# On_Board_Computer.net
KiCad netlist of a schematic drawn in EAGLE
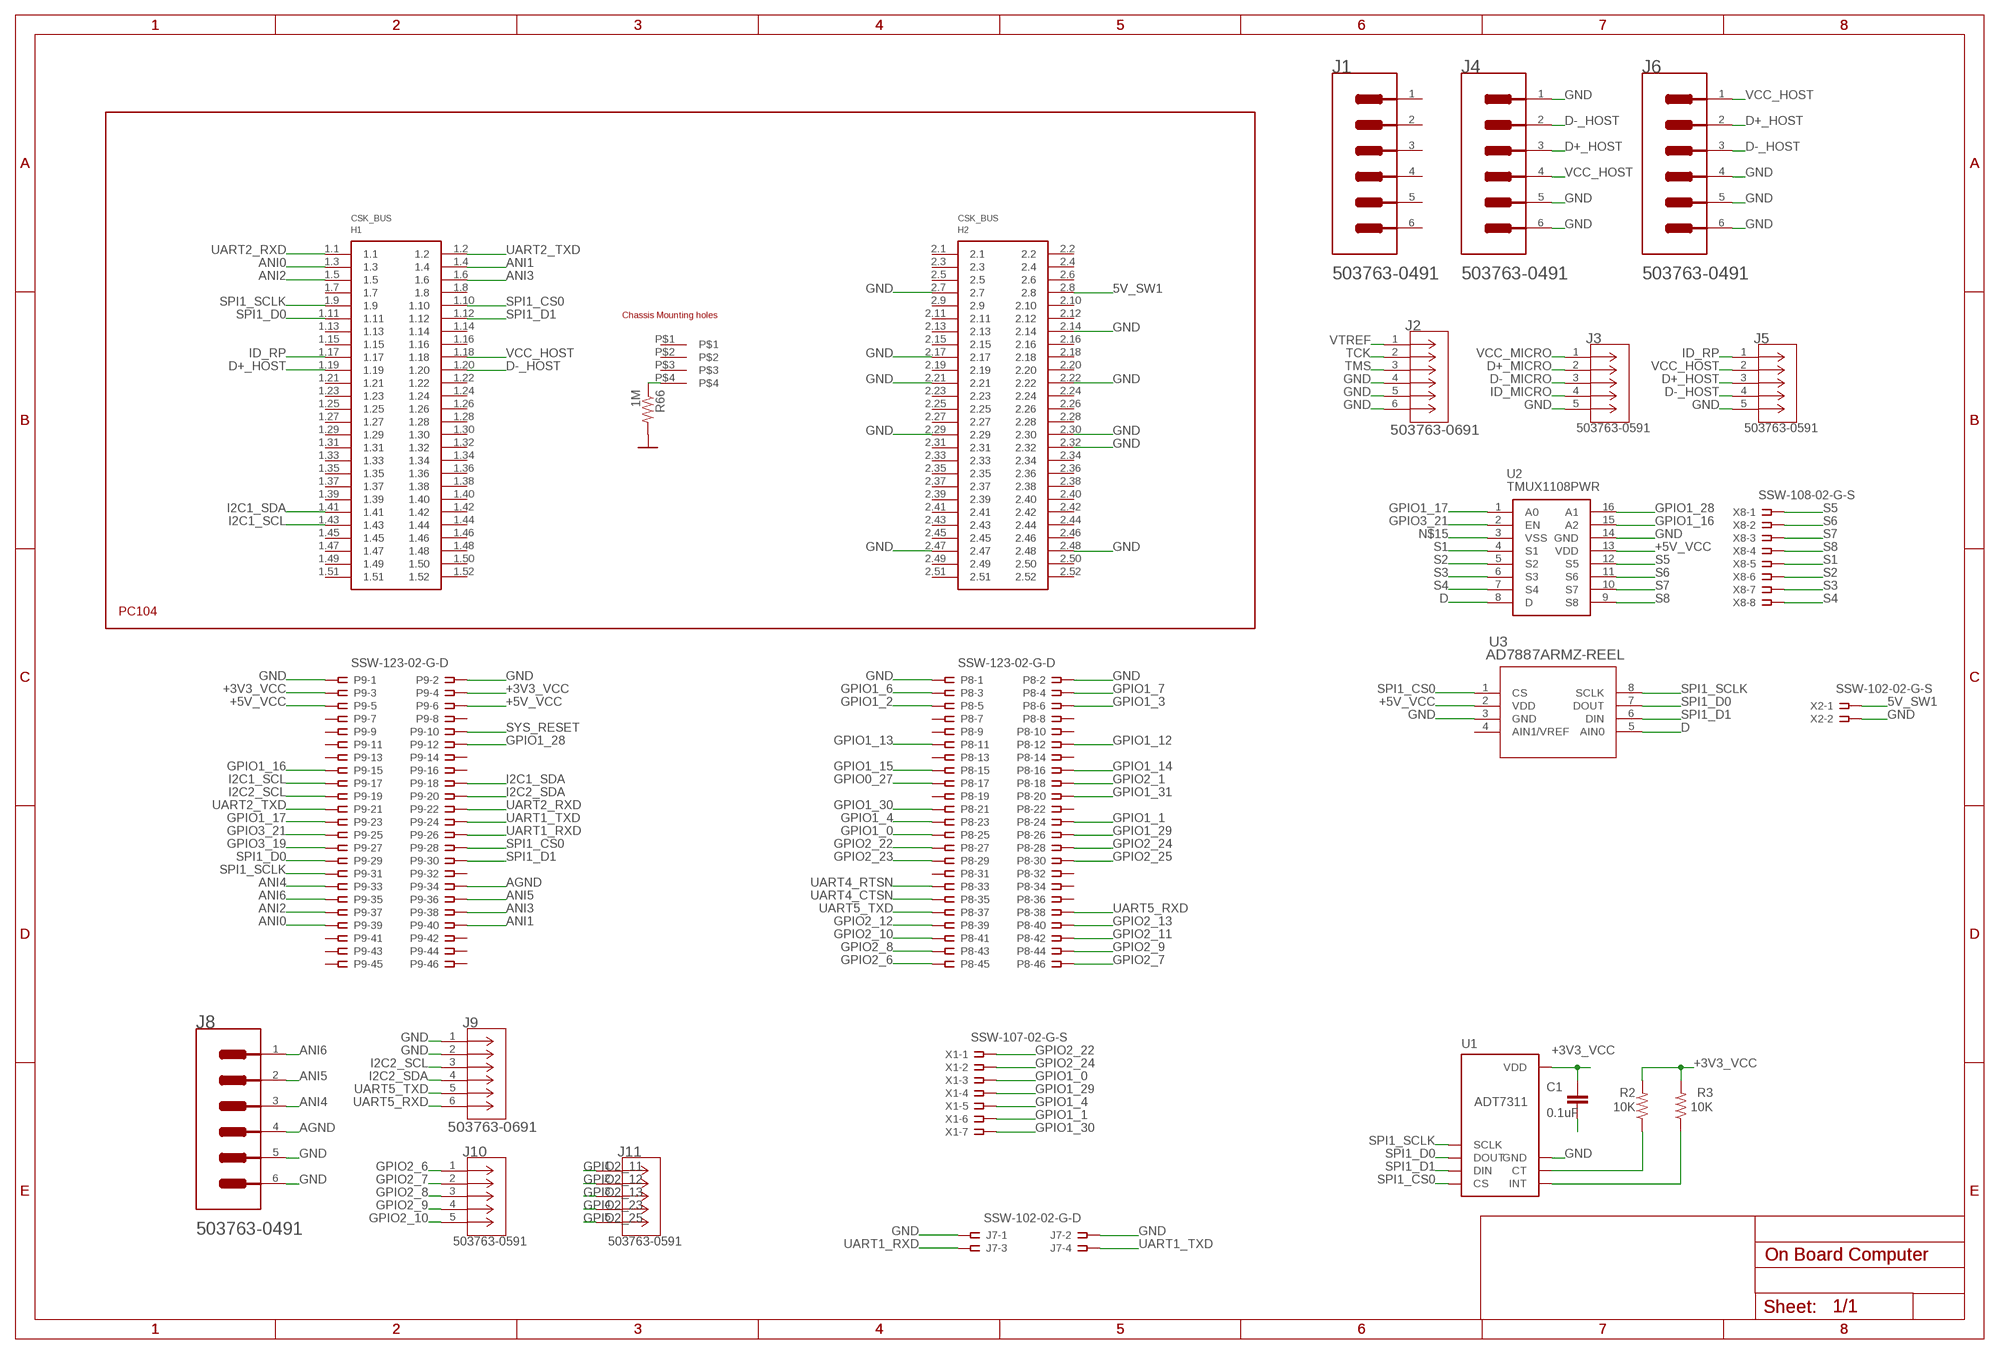
[diagram p0: schematic, sheet 1]

(export (version "E")
  (design (tool "Eeschema 10.0.6"))
  (components
    (comp (ref "C1")
      (value "0.1uF")
      (footprint "eagle-import:0805")
      (libsource (lib "eagle-import") (part "CAP0805"))
    )
    (comp (ref "H1")
      (value "PC104_WCONN")
      (footprint "eagle-import:PC104_WCONN")
      (libsource (lib "eagle-import") (part "PC104_WCONN"))
    )
    (comp (ref "J1")
      (value "MOLEX_503763-0491MOLEX_503763-0491_0_0")
      (footprint "eagle-import:MOLEX_503763-0491_0")
      (fields
        (field (name "DIGIKEY_PART_NUMBER") "WM10655CT-ND")
        (field (name "MF") "Molex")
        (field (name "MOUSER_PART_NUMBER") "538-503763-0491")
      )
      (libsource (lib "eagle-import") (part "MOLEX_503763-0491MOLEX_503763-0491_0_0"))
    )
    (comp (ref "J2")
      (value "503763-0691")
      (footprint "eagle-import:CONN_503763-0691_MOL")
      (fields (field (name "COPYRIGHT") "Copyright (C) 2018 Accelerated Designs. All rights reserved"))
      (libsource (lib "eagle-import") (part "503763-0691"))
    )
    (comp (ref "J3")
      (value "503763-0591")
      (footprint "eagle-import:CONN_5037630591_MOL")
      (fields (field (name "COPYRIGHT") "Copyright (C) 2018 Accelerated Designs. All rights reserved"))
      (libsource (lib "eagle-import") (part "503763-0591"))
    )
    (comp (ref "J4")
      (value "MOLEX_503763-0491MOLEX_503763-0491_0_0")
      (footprint "eagle-import:MOLEX_503763-0491_0")
      (fields
        (field (name "DIGIKEY_PART_NUMBER") "WM10655CT-ND")
        (field (name "MF") "Molex")
        (field (name "MOUSER_PART_NUMBER") "538-503763-0491")
      )
      (libsource (lib "eagle-import") (part "MOLEX_503763-0491MOLEX_503763-0491_0_0"))
    )
    (comp (ref "J5")
      (value "503763-0591")
      (footprint "eagle-import:CONN_5037630591_MOL")
      (fields (field (name "COPYRIGHT") "Copyright (C) 2018 Accelerated Designs. All rights reserved"))
      (libsource (lib "eagle-import") (part "503763-0591"))
    )
    (comp (ref "J6")
      (value "MOLEX_503763-0491MOLEX_503763-0491_0_0")
      (footprint "eagle-import:MOLEX_503763-0491_0")
      (fields
        (field (name "DIGIKEY_PART_NUMBER") "WM10655CT-ND")
        (field (name "MF") "Molex")
        (field (name "MOUSER_PART_NUMBER") "538-503763-0491")
      )
      (libsource (lib "eagle-import") (part "MOLEX_503763-0491MOLEX_503763-0491_0_0"))
    )
    (comp (ref "J7")
      (value "SSW-102-02-G-D")
      (footprint "eagle-import:SSW-102-02-G-D")
      (fields (field (name "MF") "Samtec Inc."))
      (libsource (lib "eagle-import") (part "SSW-102-02-G-D"))
    )
    (comp (ref "J8")
      (value "MOLEX_503763-0491MOLEX_503763-0491_0_0")
      (footprint "eagle-import:MOLEX_503763-0491_0")
      (fields
        (field (name "DIGIKEY_PART_NUMBER") "WM10655CT-ND")
        (field (name "MF") "Molex")
        (field (name "MOUSER_PART_NUMBER") "538-503763-0491")
      )
      (libsource (lib "eagle-import") (part "MOLEX_503763-0491MOLEX_503763-0491_0_0"))
    )
    (comp (ref "J9")
      (value "503763-0691")
      (footprint "eagle-import:CONN_503763-0691_MOL")
      (fields (field (name "COPYRIGHT") "Copyright (C) 2018 Accelerated Designs. All rights reserved"))
      (libsource (lib "eagle-import") (part "503763-0691"))
    )
    (comp (ref "J10")
      (value "503763-0591")
      (footprint "eagle-import:CONN_5037630591_MOL")
      (fields (field (name "COPYRIGHT") "Copyright (C) 2018 Accelerated Designs. All rights reserved"))
      (libsource (lib "eagle-import") (part "503763-0591"))
    )
    (comp (ref "J11")
      (value "503763-0591")
      (footprint "eagle-import:CONN_5037630591_MOL")
      (fields (field (name "COPYRIGHT") "Copyright (C) 2018 Accelerated Designs. All rights reserved"))
      (libsource (lib "eagle-import") (part "503763-0591"))
    )
    (comp (ref "P8")
      (value "SSW-123-02-G-D")
      (footprint "eagle-import:SSW-123-02-G-D")
      (fields (field (name "MF") "Samtec Inc."))
      (libsource (lib "eagle-import") (part "SSW-123-02-G-D"))
    )
    (comp (ref "P9")
      (value "SSW-123-02-G-D")
      (footprint "eagle-import:SSW-123-02-G-D")
      (fields (field (name "MF") "Samtec Inc."))
      (libsource (lib "eagle-import") (part "SSW-123-02-G-D"))
    )
    (comp (ref "R2")
      (value "10K")
      (footprint "eagle-import:0805")
      (libsource (lib "eagle-import") (part "RESISTOR0805-RES"))
    )
    (comp (ref "R3")
      (value "10K")
      (footprint "eagle-import:0805")
      (libsource (lib "eagle-import") (part "RESISTOR0805-RES"))
    )
    (comp (ref "R66")
      (value "1M")
      (footprint "eagle-import:0805")
      (libsource (lib "eagle-import") (part "RESISTOR0805-RES"))
    )
    (comp (ref "U1")
      (value "ADT7311")
      (footprint "eagle-import:SOIC-8")
      (libsource (lib "eagle-import") (part "ADT7311"))
    )
    (comp (ref "U2")
      (value "TMUX1108PWR")
      (footprint "eagle-import:SOP65P640X120-16N")
      (fields (field (name "MOUSER_PART_NUMBER") "595-TMUX1108PWR"))
      (libsource (lib "eagle-import") (part "TMUX1108PWR"))
    )
    (comp (ref "U3")
      (value "AD7887ARMZ-REEL")
      (footprint "eagle-import:RM_8_ADI")
      (libsource (lib "eagle-import") (part "AD7887ARMZ-REEL"))
    )
    (comp (ref "X1")
      (value "SSW-107-02-G-S")
      (footprint "eagle-import:SSW-107-02-G-S")
      (fields (field (name "MF") "Samtec Inc."))
      (libsource (lib "eagle-import") (part "SSW-107-02-G-S"))
    )
    (comp (ref "X2")
      (value "SSW-102-02-G-S")
      (footprint "eagle-import:SSW-102-02-G-S")
      (fields (field (name "MF") "Samtec Inc."))
      (libsource (lib "eagle-import") (part "SSW-102-02-G-S"))
    )
    (comp (ref "X8")
      (value "SSW-108-02-G-S")
      (footprint "eagle-import:SSW-108-02-G-S")
      (fields (field (name "MF") "Samtec Inc."))
      (libsource (lib "eagle-import") (part "SSW-108-02-G-S"))
    )
  )
  (nets
    (net (code "1") (name "/+3V3_VCC") (class "Default")
      (node (ref "C1") (pin "1") (pinfunction "1_1") (pintype "passive"))
      (node (ref "P9") (pin "3") (pinfunction "1_3") (pintype "passive"))
      (node (ref "P9") (pin "4") (pinfunction "1_4") (pintype "passive"))
      (node (ref "R2") (pin "2") (pinfunction "2_2") (pintype "passive"))
      (node (ref "R3") (pin "2") (pinfunction "2_2") (pintype "passive"))
      (node (ref "U1") (pin "8") (pinfunction "VDD_8") (pintype "bidirectional"))
    )
    (net (code "2") (name "/+5V_VCC") (class "Default")
      (node (ref "P9") (pin "5") (pinfunction "1_5") (pintype "passive"))
      (node (ref "P9") (pin "6") (pinfunction "1_6") (pintype "passive"))
      (node (ref "U2") (pin "13") (pinfunction "VDD_13") (pintype "bidirectional"))
      (node (ref "U3") (pin "2") (pinfunction "VDD_2") (pintype "power_in"))
    )
    (net (code "3") (name "/5V_SW1") (class "Default")
      (node (ref "H1") (pin "2.8") (pinfunction "2.8_2.8") (pintype "bidirectional"))
      (node (ref "X2") (pin "1") (pinfunction "1_1") (pintype "passive"))
    )
    (net (code "4") (name "/AGND") (class "Default")
      (node (ref "J8") (pin "4") (pinfunction "4_4") (pintype "passive"))
      (node (ref "P9") (pin "34") (pinfunction "1_34") (pintype "passive"))
    )
    (net (code "5") (name "/ANI0") (class "Default")
      (node (ref "H1") (pin "1.3") (pinfunction "1.3_1.3") (pintype "bidirectional"))
      (node (ref "P9") (pin "39") (pinfunction "1_39") (pintype "passive"))
    )
    (net (code "6") (name "/ANI1") (class "Default")
      (node (ref "H1") (pin "1.4") (pinfunction "1.4_1.4") (pintype "bidirectional"))
      (node (ref "P9") (pin "40") (pinfunction "1_40") (pintype "passive"))
    )
    (net (code "7") (name "/ANI2") (class "Default")
      (node (ref "H1") (pin "1.5") (pinfunction "1.5_1.5") (pintype "bidirectional"))
      (node (ref "P9") (pin "37") (pinfunction "1_37") (pintype "passive"))
    )
    (net (code "8") (name "/ANI3") (class "Default")
      (node (ref "H1") (pin "1.6") (pinfunction "1.6_1.6") (pintype "bidirectional"))
      (node (ref "P9") (pin "38") (pinfunction "1_38") (pintype "passive"))
    )
    (net (code "9") (name "/ANI4") (class "Default")
      (node (ref "J8") (pin "3") (pinfunction "3_3") (pintype "passive"))
      (node (ref "P9") (pin "33") (pinfunction "1_33") (pintype "passive"))
    )
    (net (code "10") (name "/ANI5") (class "Default")
      (node (ref "J8") (pin "2") (pinfunction "2_2") (pintype "passive"))
      (node (ref "P9") (pin "36") (pinfunction "1_36") (pintype "passive"))
    )
    (net (code "11") (name "/ANI6") (class "Default")
      (node (ref "J8") (pin "1") (pinfunction "1_1") (pintype "passive"))
      (node (ref "P9") (pin "35") (pinfunction "1_35") (pintype "passive"))
    )
    (net (code "12") (name "/D") (class "Default")
      (node (ref "U2") (pin "8") (pinfunction "D_8") (pintype "bidirectional"))
      (node (ref "U3") (pin "5") (pinfunction "AIN0_5") (pintype "passive"))
    )
    (net (code "13") (name "/D+_HOST") (class "Default")
      (node (ref "H1") (pin "1.19") (pinfunction "1.19_1.19") (pintype "bidirectional"))
      (node (ref "J4") (pin "3") (pinfunction "3_3") (pintype "passive"))
      (node (ref "J5") (pin "3") (pinfunction "3_3") (pintype "passive"))
      (node (ref "J6") (pin "2") (pinfunction "2_2") (pintype "passive"))
    )
    (net (code "14") (name "/D+_MICRO") (class "Default")
      (node (ref "J3") (pin "2") (pinfunction "2_2") (pintype "passive"))
    )
    (net (code "15") (name "/D-_HOST") (class "Default")
      (node (ref "H1") (pin "1.20") (pinfunction "1.20_1.20") (pintype "bidirectional"))
      (node (ref "J4") (pin "2") (pinfunction "2_2") (pintype "passive"))
      (node (ref "J5") (pin "4") (pinfunction "4_4") (pintype "passive"))
      (node (ref "J6") (pin "3") (pinfunction "3_3") (pintype "passive"))
    )
    (net (code "16") (name "/D-_MICRO") (class "Default")
      (node (ref "J3") (pin "3") (pinfunction "3_3") (pintype "passive"))
    )
    (net (code "17") (name "/GPIO0_27") (class "Default")
      (node (ref "P8") (pin "17") (pinfunction "1_17") (pintype "passive"))
    )
    (net (code "18") (name "/GPIO1_0") (class "Default")
      (node (ref "P8") (pin "25") (pinfunction "1_25") (pintype "passive"))
      (node (ref "X1") (pin "3") (pinfunction "1_3") (pintype "passive"))
    )
    (net (code "19") (name "/GPIO1_1") (class "Default")
      (node (ref "P8") (pin "24") (pinfunction "1_24") (pintype "passive"))
      (node (ref "X1") (pin "6") (pinfunction "1_6") (pintype "passive"))
    )
    (net (code "20") (name "/GPIO1_2") (class "Default")
      (node (ref "P8") (pin "5") (pinfunction "1_5") (pintype "passive"))
    )
    (net (code "21") (name "/GPIO1_3") (class "Default")
      (node (ref "P8") (pin "6") (pinfunction "1_6") (pintype "passive"))
    )
    (net (code "22") (name "/GPIO1_4") (class "Default")
      (node (ref "P8") (pin "23") (pinfunction "1_23") (pintype "passive"))
      (node (ref "X1") (pin "5") (pinfunction "1_5") (pintype "passive"))
    )
    (net (code "23") (name "/GPIO1_6") (class "Default")
      (node (ref "P8") (pin "3") (pinfunction "1_3") (pintype "passive"))
    )
    (net (code "24") (name "/GPIO1_7") (class "Default")
      (node (ref "P8") (pin "4") (pinfunction "1_4") (pintype "passive"))
    )
    (net (code "25") (name "/GPIO1_12") (class "Default")
      (node (ref "P8") (pin "12") (pinfunction "1_12") (pintype "passive"))
    )
    (net (code "26") (name "/GPIO1_13") (class "Default")
      (node (ref "P8") (pin "11") (pinfunction "1_11") (pintype "passive"))
    )
    (net (code "27") (name "/GPIO1_14") (class "Default")
      (node (ref "P8") (pin "16") (pinfunction "1_16") (pintype "passive"))
    )
    (net (code "28") (name "/GPIO1_15") (class "Default")
      (node (ref "P8") (pin "15") (pinfunction "1_15") (pintype "passive"))
    )
    (net (code "29") (name "/GPIO1_16") (class "Default")
      (node (ref "P9") (pin "15") (pinfunction "1_15") (pintype "passive"))
      (node (ref "U2") (pin "15") (pinfunction "A2_15") (pintype "bidirectional"))
    )
    (net (code "30") (name "/GPIO1_17") (class "Default")
      (node (ref "P9") (pin "23") (pinfunction "1_23") (pintype "passive"))
      (node (ref "U2") (pin "1") (pinfunction "A0_1") (pintype "bidirectional"))
    )
    (net (code "31") (name "/GPIO1_28") (class "Default")
      (node (ref "P9") (pin "12") (pinfunction "1_12") (pintype "passive"))
      (node (ref "U2") (pin "16") (pinfunction "A1_16") (pintype "bidirectional"))
    )
    (net (code "32") (name "/GPIO1_29") (class "Default")
      (node (ref "P8") (pin "26") (pinfunction "1_26") (pintype "passive"))
      (node (ref "X1") (pin "4") (pinfunction "1_4") (pintype "passive"))
    )
    (net (code "33") (name "/GPIO1_30") (class "Default")
      (node (ref "P8") (pin "21") (pinfunction "1_21") (pintype "passive"))
      (node (ref "X1") (pin "7") (pinfunction "1_7") (pintype "passive"))
    )
    (net (code "34") (name "/GPIO1_31") (class "Default")
      (node (ref "P8") (pin "20") (pinfunction "1_20") (pintype "passive"))
    )
    (net (code "35") (name "/GPIO2_1") (class "Default")
      (node (ref "P8") (pin "18") (pinfunction "1_18") (pintype "passive"))
    )
    (net (code "36") (name "/GPIO2_6") (class "Default")
      (node (ref "J10") (pin "1") (pinfunction "1_1") (pintype "passive"))
      (node (ref "P8") (pin "45") (pinfunction "1_45") (pintype "passive"))
    )
    (net (code "37") (name "/GPIO2_7") (class "Default")
      (node (ref "J10") (pin "2") (pinfunction "2_2") (pintype "passive"))
      (node (ref "P8") (pin "46") (pinfunction "1_46") (pintype "passive"))
    )
    (net (code "38") (name "/GPIO2_8") (class "Default")
      (node (ref "J10") (pin "3") (pinfunction "3_3") (pintype "passive"))
      (node (ref "P8") (pin "43") (pinfunction "1_43") (pintype "passive"))
    )
    (net (code "39") (name "/GPIO2_9") (class "Default")
      (node (ref "J10") (pin "4") (pinfunction "4_4") (pintype "passive"))
      (node (ref "P8") (pin "44") (pinfunction "1_44") (pintype "passive"))
    )
    (net (code "40") (name "/GPIO2_10") (class "Default")
      (node (ref "J10") (pin "5") (pinfunction "5_5") (pintype "passive"))
      (node (ref "P8") (pin "41") (pinfunction "1_41") (pintype "passive"))
    )
    (net (code "41") (name "/GPIO2_11") (class "Default")
      (node (ref "J11") (pin "1") (pinfunction "1_1") (pintype "passive"))
      (node (ref "P8") (pin "42") (pinfunction "1_42") (pintype "passive"))
    )
    (net (code "42") (name "/GPIO2_12") (class "Default")
      (node (ref "J11") (pin "2") (pinfunction "2_2") (pintype "passive"))
      (node (ref "P8") (pin "39") (pinfunction "1_39") (pintype "passive"))
    )
    (net (code "43") (name "/GPIO2_13") (class "Default")
      (node (ref "J11") (pin "3") (pinfunction "3_3") (pintype "passive"))
      (node (ref "P8") (pin "40") (pinfunction "1_40") (pintype "passive"))
    )
    (net (code "44") (name "/GPIO2_22") (class "Default")
      (node (ref "P8") (pin "27") (pinfunction "1_27") (pintype "passive"))
      (node (ref "X1") (pin "1") (pinfunction "1_1") (pintype "passive"))
    )
    (net (code "45") (name "/GPIO2_23") (class "Default")
      (node (ref "J11") (pin "4") (pinfunction "4_4") (pintype "passive"))
      (node (ref "P8") (pin "29") (pinfunction "1_29") (pintype "passive"))
    )
    (net (code "46") (name "/GPIO2_24") (class "Default")
      (node (ref "P8") (pin "28") (pinfunction "1_28") (pintype "passive"))
      (node (ref "X1") (pin "2") (pinfunction "1_2") (pintype "passive"))
    )
    (net (code "47") (name "/GPIO2_25") (class "Default")
      (node (ref "J11") (pin "5") (pinfunction "5_5") (pintype "passive"))
      (node (ref "P8") (pin "30") (pinfunction "1_30") (pintype "passive"))
    )
    (net (code "48") (name "/GPIO3_19") (class "Default")
      (node (ref "P9") (pin "27") (pinfunction "1_27") (pintype "passive"))
    )
    (net (code "49") (name "/GPIO3_21") (class "Default")
      (node (ref "P9") (pin "25") (pinfunction "1_25") (pintype "passive"))
      (node (ref "U2") (pin "2") (pinfunction "EN_2") (pintype "bidirectional"))
    )
    (net (code "50") (name "/I2C1_SCL") (class "Default")
      (node (ref "H1") (pin "1.43") (pinfunction "1.43_1.43") (pintype "bidirectional"))
      (node (ref "P9") (pin "17") (pinfunction "1_17") (pintype "passive"))
    )
    (net (code "51") (name "/I2C1_SDA") (class "Default")
      (node (ref "H1") (pin "1.41") (pinfunction "1.41_1.41") (pintype "bidirectional"))
      (node (ref "P9") (pin "18") (pinfunction "1_18") (pintype "passive"))
    )
    (net (code "52") (name "/I2C2_SCL") (class "Default")
      (node (ref "J9") (pin "3") (pinfunction "3_3") (pintype "passive"))
      (node (ref "P9") (pin "19") (pinfunction "1_19") (pintype "passive"))
    )
    (net (code "53") (name "/I2C2_SDA") (class "Default")
      (node (ref "J9") (pin "4") (pinfunction "4_4") (pintype "passive"))
      (node (ref "P9") (pin "20") (pinfunction "1_20") (pintype "passive"))
    )
    (net (code "54") (name "/ID_MICRO") (class "Default")
      (node (ref "J3") (pin "4") (pinfunction "4_4") (pintype "passive"))
    )
    (net (code "55") (name "/ID_RP") (class "Default")
      (node (ref "H1") (pin "1.17") (pinfunction "1.17_1.17") (pintype "bidirectional"))
      (node (ref "J5") (pin "1") (pinfunction "1_1") (pintype "passive"))
    )
    (net (code "56") (name "/N$15") (class "Default")
      (node (ref "U2") (pin "3") (pinfunction "VSS_3") (pintype "bidirectional"))
    )
    (net (code "57") (name "/S1") (class "Default")
      (node (ref "U2") (pin "4") (pinfunction "S1_4") (pintype "bidirectional"))
      (node (ref "X8") (pin "5") (pinfunction "1_5") (pintype "passive"))
    )
    (net (code "58") (name "/S2") (class "Default")
      (node (ref "U2") (pin "5") (pinfunction "S2_5") (pintype "bidirectional"))
      (node (ref "X8") (pin "6") (pinfunction "1_6") (pintype "passive"))
    )
    (net (code "59") (name "/S3") (class "Default")
      (node (ref "U2") (pin "6") (pinfunction "S3_6") (pintype "bidirectional"))
      (node (ref "X8") (pin "7") (pinfunction "1_7") (pintype "passive"))
    )
    (net (code "60") (name "/S4") (class "Default")
      (node (ref "U2") (pin "7") (pinfunction "S4_7") (pintype "bidirectional"))
      (node (ref "X8") (pin "8") (pinfunction "1_8") (pintype "passive"))
    )
    (net (code "61") (name "/S5") (class "Default")
      (node (ref "U2") (pin "12") (pinfunction "S5_12") (pintype "bidirectional"))
      (node (ref "X8") (pin "1") (pinfunction "1_1") (pintype "passive"))
    )
    (net (code "62") (name "/S6") (class "Default")
      (node (ref "U2") (pin "11") (pinfunction "S6_11") (pintype "bidirectional"))
      (node (ref "X8") (pin "2") (pinfunction "1_2") (pintype "passive"))
    )
    (net (code "63") (name "/S7") (class "Default")
      (node (ref "U2") (pin "10") (pinfunction "S7_10") (pintype "bidirectional"))
      (node (ref "X8") (pin "3") (pinfunction "1_3") (pintype "passive"))
    )
    (net (code "64") (name "/S8") (class "Default")
      (node (ref "U2") (pin "9") (pinfunction "S8_9") (pintype "bidirectional"))
      (node (ref "X8") (pin "4") (pinfunction "1_4") (pintype "passive"))
    )
    (net (code "65") (name "/SPI1_CS0") (class "Default")
      (node (ref "H1") (pin "1.10") (pinfunction "1.10_1.10") (pintype "bidirectional"))
      (node (ref "P9") (pin "28") (pinfunction "1_28") (pintype "passive"))
      (node (ref "U1") (pin "4") (pinfunction "CS_4") (pintype "bidirectional"))
      (node (ref "U3") (pin "1") (pinfunction "CS_1") (pintype "passive"))
    )
    (net (code "66") (name "/SPI1_D0") (class "Default")
      (node (ref "H1") (pin "1.11") (pinfunction "1.11_1.11") (pintype "bidirectional"))
      (node (ref "P9") (pin "29") (pinfunction "1_29") (pintype "passive"))
      (node (ref "U1") (pin "2") (pinfunction "DOUT_2") (pintype "bidirectional"))
      (node (ref "U3") (pin "7") (pinfunction "DOUT_7") (pintype "passive"))
    )
    (net (code "67") (name "/SPI1_D1") (class "Default")
      (node (ref "H1") (pin "1.12") (pinfunction "1.12_1.12") (pintype "bidirectional"))
      (node (ref "P9") (pin "30") (pinfunction "1_30") (pintype "passive"))
      (node (ref "U1") (pin "3") (pinfunction "DIN_3") (pintype "bidirectional"))
      (node (ref "U3") (pin "6") (pinfunction "DIN_6") (pintype "passive"))
    )
    (net (code "68") (name "/SPI1_SCLK") (class "Default")
      (node (ref "H1") (pin "1.9") (pinfunction "1.9_1.9") (pintype "bidirectional"))
      (node (ref "P9") (pin "31") (pinfunction "1_31") (pintype "passive"))
      (node (ref "U1") (pin "1") (pinfunction "SCLK_1") (pintype "bidirectional"))
      (node (ref "U3") (pin "8") (pinfunction "SCLK_8") (pintype "passive"))
    )
    (net (code "69") (name "/SYS_RESET") (class "Default")
      (node (ref "P9") (pin "10") (pinfunction "1_10") (pintype "passive"))
    )
    (net (code "70") (name "/TCK") (class "Default")
      (node (ref "J2") (pin "2") (pinfunction "2_2") (pintype "passive"))
    )
    (net (code "71") (name "/TMS") (class "Default")
      (node (ref "J2") (pin "3") (pinfunction "3_3") (pintype "passive"))
    )
    (net (code "72") (name "/UART1_RXD") (class "Default")
      (node (ref "J7") (pin "3") (pinfunction "1_3") (pintype "passive"))
      (node (ref "P9") (pin "26") (pinfunction "1_26") (pintype "passive"))
    )
    (net (code "73") (name "/UART1_TXD") (class "Default")
      (node (ref "J7") (pin "4") (pinfunction "1_4") (pintype "passive"))
      (node (ref "P9") (pin "24") (pinfunction "1_24") (pintype "passive"))
    )
    (net (code "74") (name "/UART2_RXD") (class "Default")
      (node (ref "H1") (pin "1.1") (pinfunction "1.1_1.1") (pintype "bidirectional"))
      (node (ref "P9") (pin "22") (pinfunction "1_22") (pintype "passive"))
    )
    (net (code "75") (name "/UART2_TXD") (class "Default")
      (node (ref "H1") (pin "1.2") (pinfunction "1.2_1.2") (pintype "bidirectional"))
      (node (ref "P9") (pin "21") (pinfunction "1_21") (pintype "passive"))
    )
    (net (code "76") (name "/UART4_CTSN") (class "Default")
      (node (ref "P8") (pin "35") (pinfunction "1_35") (pintype "passive"))
    )
    (net (code "77") (name "/UART4_RTSN") (class "Default")
      (node (ref "P8") (pin "33") (pinfunction "1_33") (pintype "passive"))
    )
    (net (code "78") (name "/UART5_RXD") (class "Default")
      (node (ref "J9") (pin "6") (pinfunction "6_6") (pintype "passive"))
      (node (ref "P8") (pin "38") (pinfunction "1_38") (pintype "passive"))
    )
    (net (code "79") (name "/UART5_TXD") (class "Default")
      (node (ref "J9") (pin "5") (pinfunction "5_5") (pintype "passive"))
      (node (ref "P8") (pin "37") (pinfunction "1_37") (pintype "passive"))
    )
    (net (code "80") (name "/VCC_HOST") (class "Default")
      (node (ref "H1") (pin "1.18") (pinfunction "1.18_1.18") (pintype "bidirectional"))
      (node (ref "J4") (pin "4") (pinfunction "4_4") (pintype "passive"))
      (node (ref "J5") (pin "2") (pinfunction "2_2") (pintype "passive"))
      (node (ref "J6") (pin "1") (pinfunction "1_1") (pintype "passive"))
    )
    (net (code "81") (name "/VCC_MICRO") (class "Default")
      (node (ref "J3") (pin "1") (pinfunction "1_1") (pintype "passive"))
    )
    (net (code "82") (name "/VTREF") (class "Default")
      (node (ref "J2") (pin "1") (pinfunction "1_1") (pintype "passive"))
    )
    (net (code "83") (name "GND") (class "Default")
      (node (ref "C1") (pin "2") (pinfunction "2_2") (pintype "passive"))
      (node (ref "H1") (pin "2.14") (pinfunction "2.14_2.14") (pintype "bidirectional"))
      (node (ref "H1") (pin "2.17") (pinfunction "2.17_2.17") (pintype "bidirectional"))
      (node (ref "H1") (pin "2.21") (pinfunction "2.21_2.21") (pintype "bidirectional"))
      (node (ref "H1") (pin "2.22") (pinfunction "2.22_2.22") (pintype "bidirectional"))
      (node (ref "H1") (pin "2.29") (pinfunction "2.29_2.29") (pintype "bidirectional"))
      (node (ref "H1") (pin "2.30") (pinfunction "2.30_2.30") (pintype "bidirectional"))
      (node (ref "H1") (pin "2.32") (pinfunction "2.32_2.32") (pintype "bidirectional"))
      (node (ref "H1") (pin "2.47") (pinfunction "2.47_2.47") (pintype "bidirectional"))
      (node (ref "H1") (pin "2.48") (pinfunction "2.48_2.48") (pintype "bidirectional"))
      (node (ref "H1") (pin "2.7") (pinfunction "2.7_2.7") (pintype "bidirectional"))
      (node (ref "J2") (pin "4") (pinfunction "4_4") (pintype "passive"))
      (node (ref "J2") (pin "5") (pinfunction "5_5") (pintype "passive"))
      (node (ref "J2") (pin "6") (pinfunction "6_6") (pintype "passive"))
      (node (ref "J3") (pin "5") (pinfunction "5_5") (pintype "passive"))
      (node (ref "J4") (pin "1") (pinfunction "1_1") (pintype "passive"))
      (node (ref "J4") (pin "5") (pinfunction "MNT_1_5") (pintype "passive"))
      (node (ref "J4") (pin "6") (pinfunction "MNT_2_6") (pintype "passive"))
      (node (ref "J5") (pin "5") (pinfunction "5_5") (pintype "passive"))
      (node (ref "J6") (pin "4") (pinfunction "4_4") (pintype "passive"))
      (node (ref "J6") (pin "5") (pinfunction "MNT_1_5") (pintype "passive"))
      (node (ref "J6") (pin "6") (pinfunction "MNT_2_6") (pintype "passive"))
      (node (ref "J7") (pin "1") (pinfunction "1_1") (pintype "passive"))
      (node (ref "J7") (pin "2") (pinfunction "1_2") (pintype "passive"))
      (node (ref "J8") (pin "5") (pinfunction "MNT_1_5") (pintype "passive"))
      (node (ref "J8") (pin "6") (pinfunction "MNT_2_6") (pintype "passive"))
      (node (ref "J9") (pin "1") (pinfunction "1_1") (pintype "passive"))
      (node (ref "J9") (pin "2") (pinfunction "2_2") (pintype "passive"))
      (node (ref "P8") (pin "1") (pinfunction "1_1") (pintype "passive"))
      (node (ref "P8") (pin "2") (pinfunction "1_2") (pintype "passive"))
      (node (ref "P9") (pin "1") (pinfunction "1_1") (pintype "passive"))
      (node (ref "P9") (pin "2") (pinfunction "1_2") (pintype "passive"))
      (node (ref "R66") (pin "2") (pinfunction "2_2") (pintype "passive"))
      (node (ref "U1") (pin "7") (pinfunction "GND_7") (pintype "bidirectional"))
      (node (ref "U2") (pin "14") (pinfunction "GND_14") (pintype "bidirectional"))
      (node (ref "U3") (pin "3") (pinfunction "GND_3") (pintype "passive"))
      (node (ref "X2") (pin "2") (pinfunction "1_2") (pintype "passive"))
    )
    (net (code "84") (name "Net-(H1-PadP$4)") (class "Default")
      (node (ref "H1") (pin "P$4") (pinfunction "P$4_P$4") (pintype "bidirectional"))
      (node (ref "R66") (pin "1") (pinfunction "1_1") (pintype "passive"))
    )
    (net (code "85") (name "Net-(U1-CT)") (class "Default")
      (node (ref "R2") (pin "1") (pinfunction "1_1") (pintype "passive"))
      (node (ref "U1") (pin "6") (pinfunction "CT_6") (pintype "bidirectional"))
    )
    (net (code "86") (name "Net-(U1-INT)") (class "Default")
      (node (ref "R3") (pin "1") (pinfunction "1_1") (pintype "passive"))
      (node (ref "U1") (pin "5") (pinfunction "INT_5") (pintype "bidirectional"))
    )
    (net (code "87") (name "unconnected-(H1-Pad1.7)") (class "Default")
      (node (ref "H1") (pin "1.7") (pinfunction "1.7_1.7") (pintype "bidirectional"))
    )
    (net (code "88") (name "unconnected-(H1-Pad1.8)") (class "Default")
      (node (ref "H1") (pin "1.8") (pinfunction "1.8_1.8") (pintype "bidirectional"))
    )
    (net (code "89") (name "unconnected-(H1-Pad1.13)") (class "Default")
      (node (ref "H1") (pin "1.13") (pinfunction "1.13_1.13") (pintype "bidirectional"))
    )
    (net (code "90") (name "unconnected-(H1-Pad1.14)") (class "Default")
      (node (ref "H1") (pin "1.14") (pinfunction "1.14_1.14") (pintype "bidirectional"))
    )
    (net (code "91") (name "unconnected-(H1-Pad1.15)") (class "Default")
      (node (ref "H1") (pin "1.15") (pinfunction "1.15_1.15") (pintype "bidirectional"))
    )
    (net (code "92") (name "unconnected-(H1-Pad1.16)") (class "Default")
      (node (ref "H1") (pin "1.16") (pinfunction "1.16_1.16") (pintype "bidirectional"))
    )
    (net (code "93") (name "unconnected-(H1-Pad1.21)") (class "Default")
      (node (ref "H1") (pin "1.21") (pinfunction "1.21_1.21") (pintype "bidirectional"))
    )
    (net (code "94") (name "unconnected-(H1-Pad1.22)") (class "Default")
      (node (ref "H1") (pin "1.22") (pinfunction "1.22_1.22") (pintype "bidirectional"))
    )
    (net (code "95") (name "unconnected-(H1-Pad1.23)") (class "Default")
      (node (ref "H1") (pin "1.23") (pinfunction "1.23_1.23") (pintype "bidirectional"))
    )
    (net (code "96") (name "unconnected-(H1-Pad1.24)") (class "Default")
      (node (ref "H1") (pin "1.24") (pinfunction "1.24_1.24") (pintype "bidirectional"))
    )
    (net (code "97") (name "unconnected-(H1-Pad1.25)") (class "Default")
      (node (ref "H1") (pin "1.25") (pinfunction "1.25_1.25") (pintype "bidirectional"))
    )
    (net (code "98") (name "unconnected-(H1-Pad1.26)") (class "Default")
      (node (ref "H1") (pin "1.26") (pinfunction "1.26_1.26") (pintype "bidirectional"))
    )
    (net (code "99") (name "unconnected-(H1-Pad1.27)") (class "Default")
      (node (ref "H1") (pin "1.27") (pinfunction "1.27_1.27") (pintype "bidirectional"))
    )
    (net (code "100") (name "unconnected-(H1-Pad1.28)") (class "Default")
      (node (ref "H1") (pin "1.28") (pinfunction "1.28_1.28") (pintype "bidirectional"))
    )
    (net (code "101") (name "unconnected-(H1-Pad1.29)") (class "Default")
      (node (ref "H1") (pin "1.29") (pinfunction "1.29_1.29") (pintype "bidirectional"))
    )
    (net (code "102") (name "unconnected-(H1-Pad1.30)") (class "Default")
      (node (ref "H1") (pin "1.30") (pinfunction "1.30_1.30") (pintype "bidirectional"))
    )
    (net (code "103") (name "unconnected-(H1-Pad1.31)") (class "Default")
      (node (ref "H1") (pin "1.31") (pinfunction "1.31_1.31") (pintype "bidirectional"))
    )
    (net (code "104") (name "unconnected-(H1-Pad1.32)") (class "Default")
      (node (ref "H1") (pin "1.32") (pinfunction "1.32_1.32") (pintype "bidirectional"))
    )
    (net (code "105") (name "unconnected-(H1-Pad1.33)") (class "Default")
      (node (ref "H1") (pin "1.33") (pinfunction "1.33_1.33") (pintype "bidirectional"))
    )
    (net (code "106") (name "unconnected-(H1-Pad1.34)") (class "Default")
      (node (ref "H1") (pin "1.34") (pinfunction "1.34_1.34") (pintype "bidirectional"))
    )
    (net (code "107") (name "unconnected-(H1-Pad1.35)") (class "Default")
      (node (ref "H1") (pin "1.35") (pinfunction "1.35_1.35") (pintype "bidirectional"))
    )
    (net (code "108") (name "unconnected-(H1-Pad1.36)") (class "Default")
      (node (ref "H1") (pin "1.36") (pinfunction "1.36_1.36") (pintype "bidirectional"))
    )
    (net (code "109") (name "unconnected-(H1-Pad1.37)") (class "Default")
      (node (ref "H1") (pin "1.37") (pinfunction "1.37_1.37") (pintype "bidirectional"))
    )
    (net (code "110") (name "unconnected-(H1-Pad1.38)") (class "Default")
      (node (ref "H1") (pin "1.38") (pinfunction "1.38_1.38") (pintype "bidirectional"))
    )
    (net (code "111") (name "unconnected-(H1-Pad1.39)") (class "Default")
      (node (ref "H1") (pin "1.39") (pinfunction "1.39_1.39") (pintype "bidirectional"))
    )
    (net (code "112") (name "unconnected-(H1-Pad1.40)") (class "Default")
      (node (ref "H1") (pin "1.40") (pinfunction "1.40_1.40") (pintype "bidirectional"))
    )
    (net (code "113") (name "unconnected-(H1-Pad1.42)") (class "Default")
      (node (ref "H1") (pin "1.42") (pinfunction "1.42_1.42") (pintype "bidirectional"))
    )
    (net (code "114") (name "unconnected-(H1-Pad1.44)") (class "Default")
      (node (ref "H1") (pin "1.44") (pinfunction "1.44_1.44") (pintype "bidirectional"))
    )
    (net (code "115") (name "unconnected-(H1-Pad1.45)") (class "Default")
      (node (ref "H1") (pin "1.45") (pinfunction "1.45_1.45") (pintype "bidirectional"))
    )
    (net (code "116") (name "unconnected-(H1-Pad1.46)") (class "Default")
      (node (ref "H1") (pin "1.46") (pinfunction "1.46_1.46") (pintype "bidirectional"))
    )
    (net (code "117") (name "unconnected-(H1-Pad1.47)") (class "Default")
      (node (ref "H1") (pin "1.47") (pinfunction "1.47_1.47") (pintype "bidirectional"))
    )
    (net (code "118") (name "unconnected-(H1-Pad1.48)") (class "Default")
      (node (ref "H1") (pin "1.48") (pinfunction "1.48_1.48") (pintype "bidirectional"))
    )
    (net (code "119") (name "unconnected-(H1-Pad1.49)") (class "Default")
      (node (ref "H1") (pin "1.49") (pinfunction "1.49_1.49") (pintype "bidirectional"))
    )
    (net (code "120") (name "unconnected-(H1-Pad1.50)") (class "Default")
      (node (ref "H1") (pin "1.50") (pinfunction "1.50_1.50") (pintype "bidirectional"))
    )
    (net (code "121") (name "unconnected-(H1-Pad1.51)") (class "Default")
      (node (ref "H1") (pin "1.51") (pinfunction "1.51_1.51") (pintype "bidirectional"))
    )
    (net (code "122") (name "unconnected-(H1-Pad1.52)") (class "Default")
      (node (ref "H1") (pin "1.52") (pinfunction "1.52_1.52") (pintype "bidirectional"))
    )
    (net (code "123") (name "unconnected-(H1-Pad2.1)") (class "Default")
      (node (ref "H1") (pin "2.1") (pinfunction "2.1_2.1") (pintype "bidirectional"))
    )
    (net (code "124") (name "unconnected-(H1-Pad2.2)") (class "Default")
      (node (ref "H1") (pin "2.2") (pinfunction "2.2_2.2") (pintype "bidirectional"))
    )
    (net (code "125") (name "unconnected-(H1-Pad2.3)") (class "Default")
      (node (ref "H1") (pin "2.3") (pinfunction "2.3_2.3") (pintype "bidirectional"))
    )
    (net (code "126") (name "unconnected-(H1-Pad2.4)") (class "Default")
      (node (ref "H1") (pin "2.4") (pinfunction "2.4_2.4") (pintype "bidirectional"))
    )
    (net (code "127") (name "unconnected-(H1-Pad2.5)") (class "Default")
      (node (ref "H1") (pin "2.5") (pinfunction "2.5_2.5") (pintype "bidirectional"))
    )
    (net (code "128") (name "unconnected-(H1-Pad2.6)") (class "Default")
      (node (ref "H1") (pin "2.6") (pinfunction "2.6_2.6") (pintype "bidirectional"))
    )
    (net (code "129") (name "unconnected-(H1-Pad2.9)") (class "Default")
      (node (ref "H1") (pin "2.9") (pinfunction "2.9_2.9") (pintype "bidirectional"))
    )
    (net (code "130") (name "unconnected-(H1-Pad2.10)") (class "Default")
      (node (ref "H1") (pin "2.10") (pinfunction "2.10_2.10") (pintype "bidirectional"))
    )
    (net (code "131") (name "unconnected-(H1-Pad2.11)") (class "Default")
      (node (ref "H1") (pin "2.11") (pinfunction "2.11_2.11") (pintype "bidirectional"))
    )
    (net (code "132") (name "unconnected-(H1-Pad2.12)") (class "Default")
      (node (ref "H1") (pin "2.12") (pinfunction "2.12_2.12") (pintype "bidirectional"))
    )
    (net (code "133") (name "unconnected-(H1-Pad2.13)") (class "Default")
      (node (ref "H1") (pin "2.13") (pinfunction "2.13_2.13") (pintype "bidirectional"))
    )
    (net (code "134") (name "unconnected-(H1-Pad2.15)") (class "Default")
      (node (ref "H1") (pin "2.15") (pinfunction "2.15_2.15") (pintype "bidirectional"))
    )
    (net (code "135") (name "unconnected-(H1-Pad2.16)") (class "Default")
      (node (ref "H1") (pin "2.16") (pinfunction "2.16_2.16") (pintype "bidirectional"))
    )
    (net (code "136") (name "unconnected-(H1-Pad2.18)") (class "Default")
      (node (ref "H1") (pin "2.18") (pinfunction "2.18_2.18") (pintype "bidirectional"))
    )
    (net (code "137") (name "unconnected-(H1-Pad2.19)") (class "Default")
      (node (ref "H1") (pin "2.19") (pinfunction "2.19_2.19") (pintype "bidirectional"))
    )
    (net (code "138") (name "unconnected-(H1-Pad2.20)") (class "Default")
      (node (ref "H1") (pin "2.20") (pinfunction "2.20_2.20") (pintype "bidirectional"))
    )
    (net (code "139") (name "unconnected-(H1-Pad2.23)") (class "Default")
      (node (ref "H1") (pin "2.23") (pinfunction "2.23_2.23") (pintype "bidirectional"))
    )
    (net (code "140") (name "unconnected-(H1-Pad2.24)") (class "Default")
      (node (ref "H1") (pin "2.24") (pinfunction "2.24_2.24") (pintype "bidirectional"))
    )
    (net (code "141") (name "unconnected-(H1-Pad2.25)") (class "Default")
      (node (ref "H1") (pin "2.25") (pinfunction "2.25_2.25") (pintype "bidirectional"))
    )
    (net (code "142") (name "unconnected-(H1-Pad2.26)") (class "Default")
      (node (ref "H1") (pin "2.26") (pinfunction "2.26_2.26") (pintype "bidirectional"))
    )
    (net (code "143") (name "unconnected-(H1-Pad2.27)") (class "Default")
      (node (ref "H1") (pin "2.27") (pinfunction "2.27_2.27") (pintype "bidirectional"))
    )
    (net (code "144") (name "unconnected-(H1-Pad2.28)") (class "Default")
      (node (ref "H1") (pin "2.28") (pinfunction "2.28_2.28") (pintype "bidirectional"))
    )
    (net (code "145") (name "unconnected-(H1-Pad2.31)") (class "Default")
      (node (ref "H1") (pin "2.31") (pinfunction "2.31_2.31") (pintype "bidirectional"))
    )
    (net (code "146") (name "unconnected-(H1-Pad2.33)") (class "Default")
      (node (ref "H1") (pin "2.33") (pinfunction "2.33_2.33") (pintype "bidirectional"))
    )
    (net (code "147") (name "unconnected-(H1-Pad2.34)") (class "Default")
      (node (ref "H1") (pin "2.34") (pinfunction "2.34_2.34") (pintype "bidirectional"))
    )
    (net (code "148") (name "unconnected-(H1-Pad2.35)") (class "Default")
      (node (ref "H1") (pin "2.35") (pinfunction "2.35_2.35") (pintype "bidirectional"))
    )
    (net (code "149") (name "unconnected-(H1-Pad2.36)") (class "Default")
      (node (ref "H1") (pin "2.36") (pinfunction "2.36_2.36") (pintype "bidirectional"))
    )
    (net (code "150") (name "unconnected-(H1-Pad2.37)") (class "Default")
      (node (ref "H1") (pin "2.37") (pinfunction "2.37_2.37") (pintype "bidirectional"))
    )
    (net (code "151") (name "unconnected-(H1-Pad2.38)") (class "Default")
      (node (ref "H1") (pin "2.38") (pinfunction "2.38_2.38") (pintype "bidirectional"))
    )
    (net (code "152") (name "unconnected-(H1-Pad2.39)") (class "Default")
      (node (ref "H1") (pin "2.39") (pinfunction "2.39_2.39") (pintype "bidirectional"))
    )
    (net (code "153") (name "unconnected-(H1-Pad2.40)") (class "Default")
      (node (ref "H1") (pin "2.40") (pinfunction "2.40_2.40") (pintype "bidirectional"))
    )
    (net (code "154") (name "unconnected-(H1-Pad2.41)") (class "Default")
      (node (ref "H1") (pin "2.41") (pinfunction "2.41_2.41") (pintype "bidirectional"))
    )
    (net (code "155") (name "unconnected-(H1-Pad2.42)") (class "Default")
      (node (ref "H1") (pin "2.42") (pinfunction "2.42_2.42") (pintype "bidirectional"))
    )
    (net (code "156") (name "unconnected-(H1-Pad2.43)") (class "Default")
      (node (ref "H1") (pin "2.43") (pinfunction "2.43_2.43") (pintype "bidirectional"))
    )
    (net (code "157") (name "unconnected-(H1-Pad2.44)") (class "Default")
      (node (ref "H1") (pin "2.44") (pinfunction "2.44_2.44") (pintype "bidirectional"))
    )
    (net (code "158") (name "unconnected-(H1-Pad2.45)") (class "Default")
      (node (ref "H1") (pin "2.45") (pinfunction "2.45_2.45") (pintype "bidirectional"))
    )
    (net (code "159") (name "unconnected-(H1-Pad2.46)") (class "Default")
      (node (ref "H1") (pin "2.46") (pinfunction "2.46_2.46") (pintype "bidirectional"))
    )
    (net (code "160") (name "unconnected-(H1-Pad2.49)") (class "Default")
      (node (ref "H1") (pin "2.49") (pinfunction "2.49_2.49") (pintype "bidirectional"))
    )
    (net (code "161") (name "unconnected-(H1-Pad2.50)") (class "Default")
      (node (ref "H1") (pin "2.50") (pinfunction "2.50_2.50") (pintype "bidirectional"))
    )
    (net (code "162") (name "unconnected-(H1-Pad2.51)") (class "Default")
      (node (ref "H1") (pin "2.51") (pinfunction "2.51_2.51") (pintype "bidirectional"))
    )
    (net (code "163") (name "unconnected-(H1-Pad2.52)") (class "Default")
      (node (ref "H1") (pin "2.52") (pinfunction "2.52_2.52") (pintype "bidirectional"))
    )
    (net (code "164") (name "unconnected-(H1-PadP$1)") (class "Default")
      (node (ref "H1") (pin "P$1") (pinfunction "P$1_P$1") (pintype "bidirectional"))
    )
    (net (code "165") (name "unconnected-(H1-PadP$2)") (class "Default")
      (node (ref "H1") (pin "P$2") (pinfunction "P$2_P$2") (pintype "bidirectional"))
    )
    (net (code "166") (name "unconnected-(H1-PadP$3)") (class "Default")
      (node (ref "H1") (pin "P$3") (pinfunction "P$3_P$3") (pintype "bidirectional"))
    )
    (net (code "167") (name "unconnected-(J1-MNT_1-Pad5)") (class "Default")
      (node (ref "J1") (pin "5") (pinfunction "MNT_1_5") (pintype "passive"))
    )
    (net (code "168") (name "unconnected-(J1-MNT_2-Pad6)") (class "Default")
      (node (ref "J1") (pin "6") (pinfunction "MNT_2_6") (pintype "passive"))
    )
    (net (code "169") (name "unconnected-(J1-Pad1)") (class "Default")
      (node (ref "J1") (pin "1") (pinfunction "1_1") (pintype "passive"))
    )
    (net (code "170") (name "unconnected-(J1-Pad2)") (class "Default")
      (node (ref "J1") (pin "2") (pinfunction "2_2") (pintype "passive"))
    )
    (net (code "171") (name "unconnected-(J1-Pad3)") (class "Default")
      (node (ref "J1") (pin "3") (pinfunction "3_3") (pintype "passive"))
    )
    (net (code "172") (name "unconnected-(J1-Pad4)") (class "Default")
      (node (ref "J1") (pin "4") (pinfunction "4_4") (pintype "passive"))
    )
    (net (code "173") (name "unconnected-(P8AB-1-Pad34)") (class "Default")
      (node (ref "P8") (pin "34") (pinfunction "1_34") (pintype "passive"))
    )
    (net (code "174") (name "unconnected-(P8AD-1-Pad36)") (class "Default")
      (node (ref "P8") (pin "36") (pinfunction "1_36") (pintype "passive"))
    )
    (net (code "175") (name "unconnected-(P8AR-1-Pad7)") (class "Default")
      (node (ref "P8") (pin "7") (pinfunction "1_7") (pintype "passive"))
    )
    (net (code "176") (name "unconnected-(P8AS-1-Pad8)") (class "Default")
      (node (ref "P8") (pin "8") (pinfunction "1_8") (pintype "passive"))
    )
    (net (code "177") (name "unconnected-(P8AT-1-Pad9)") (class "Default")
      (node (ref "P8") (pin "9") (pinfunction "1_9") (pintype "passive"))
    )
    (net (code "178") (name "unconnected-(P8B-1-Pad10)") (class "Default")
      (node (ref "P8") (pin "10") (pinfunction "1_10") (pintype "passive"))
    )
    (net (code "179") (name "unconnected-(P8E-1-Pad13)") (class "Default")
      (node (ref "P8") (pin "13") (pinfunction "1_13") (pintype "passive"))
    )
    (net (code "180") (name "unconnected-(P8F-1-Pad14)") (class "Default")
      (node (ref "P8") (pin "14") (pinfunction "1_14") (pintype "passive"))
    )
    (net (code "181") (name "unconnected-(P8K-1-Pad19)") (class "Default")
      (node (ref "P8") (pin "19") (pinfunction "1_19") (pintype "passive"))
    )
    (net (code "182") (name "unconnected-(P8O-1-Pad22)") (class "Default")
      (node (ref "P8") (pin "22") (pinfunction "1_22") (pintype "passive"))
    )
    (net (code "183") (name "unconnected-(P8Y-1-Pad31)") (class "Default")
      (node (ref "P8") (pin "31") (pinfunction "1_31") (pintype "passive"))
    )
    (net (code "184") (name "unconnected-(P8Z-1-Pad32)") (class "Default")
      (node (ref "P8") (pin "32") (pinfunction "1_32") (pintype "passive"))
    )
    (net (code "185") (name "unconnected-(P9AJ-1-Pad41)") (class "Default")
      (node (ref "P9") (pin "41") (pinfunction "1_41") (pintype "passive"))
    )
    (net (code "186") (name "unconnected-(P9AK-1-Pad42)") (class "Default")
      (node (ref "P9") (pin "42") (pinfunction "1_42") (pintype "passive"))
    )
    (net (code "187") (name "unconnected-(P9AL-1-Pad43)") (class "Default")
      (node (ref "P9") (pin "43") (pinfunction "1_43") (pintype "passive"))
    )
    (net (code "188") (name "unconnected-(P9AM-1-Pad44)") (class "Default")
      (node (ref "P9") (pin "44") (pinfunction "1_44") (pintype "passive"))
    )
    (net (code "189") (name "unconnected-(P9AN-1-Pad45)") (class "Default")
      (node (ref "P9") (pin "45") (pinfunction "1_45") (pintype "passive"))
    )
    (net (code "190") (name "unconnected-(P9AO-1-Pad46)") (class "Default")
      (node (ref "P9") (pin "46") (pinfunction "1_46") (pintype "passive"))
    )
    (net (code "191") (name "unconnected-(P9AR-1-Pad7)") (class "Default")
      (node (ref "P9") (pin "7") (pinfunction "1_7") (pintype "passive"))
    )
    (net (code "192") (name "unconnected-(P9AS-1-Pad8)") (class "Default")
      (node (ref "P9") (pin "8") (pinfunction "1_8") (pintype "passive"))
    )
    (net (code "193") (name "unconnected-(P9AT-1-Pad9)") (class "Default")
      (node (ref "P9") (pin "9") (pinfunction "1_9") (pintype "passive"))
    )
    (net (code "194") (name "unconnected-(P9C-1-Pad11)") (class "Default")
      (node (ref "P9") (pin "11") (pinfunction "1_11") (pintype "passive"))
    )
    (net (code "195") (name "unconnected-(P9E-1-Pad13)") (class "Default")
      (node (ref "P9") (pin "13") (pinfunction "1_13") (pintype "passive"))
    )
    (net (code "196") (name "unconnected-(P9F-1-Pad14)") (class "Default")
      (node (ref "P9") (pin "14") (pinfunction "1_14") (pintype "passive"))
    )
    (net (code "197") (name "unconnected-(P9H-1-Pad16)") (class "Default")
      (node (ref "P9") (pin "16") (pinfunction "1_16") (pintype "passive"))
    )
    (net (code "198") (name "unconnected-(P9Z-1-Pad32)") (class "Default")
      (node (ref "P9") (pin "32") (pinfunction "1_32") (pintype "passive"))
    )
    (net (code "199") (name "unconnected-(U3-AIN1{slash}VREF-Pad4)") (class "Default")
      (node (ref "U3") (pin "4") (pinfunction "AIN1/VREF_4") (pintype "passive"))
    )
  )
)
